# KeyboardMainMCU.net
KiCad netlist of a schematic drawn in Altium Designer
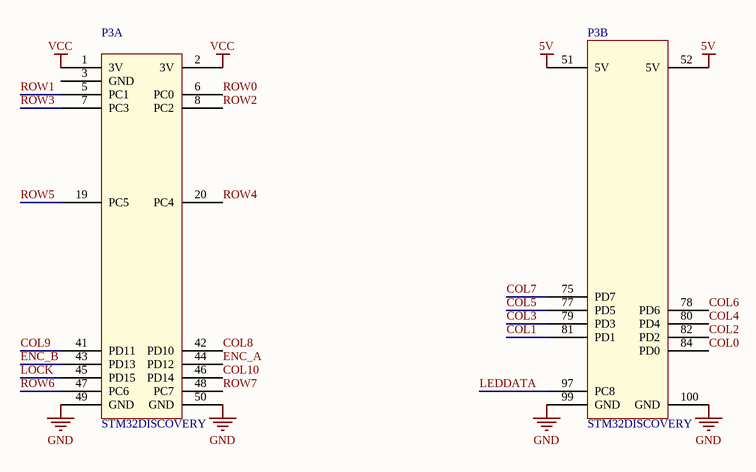
[diagram p0: KeyboardMainMCU.SchDoc]

(export (version "E")
  (design (tool "Eeschema 10.0.6"))
  (components
    (comp (ref "P3")
      (value "STM32DISCOVERY")
      (footprint "DISCO")
      (libsource (lib "OSA") (part "STM32DISCOVERY"))
    )
  )
  (nets
    (net (code "1") (name "/COL0") (class "Default")
      (node (ref "P3") (pin "84") (pinfunction "PD0_84") (pintype "passive"))
    )
    (net (code "2") (name "/COL1") (class "Default")
      (node (ref "P3") (pin "81") (pinfunction "PD1_81") (pintype "passive"))
    )
    (net (code "3") (name "/COL2") (class "Default")
      (node (ref "P3") (pin "82") (pinfunction "PD2_82") (pintype "passive"))
    )
    (net (code "4") (name "/COL3") (class "Default")
      (node (ref "P3") (pin "79") (pinfunction "PD3_79") (pintype "passive"))
    )
    (net (code "5") (name "/COL4") (class "Default")
      (node (ref "P3") (pin "80") (pinfunction "PD4_80") (pintype "passive"))
    )
    (net (code "6") (name "/COL5") (class "Default")
      (node (ref "P3") (pin "77") (pinfunction "PD5_77") (pintype "passive"))
    )
    (net (code "7") (name "/COL6") (class "Default")
      (node (ref "P3") (pin "78") (pinfunction "PD6_78") (pintype "passive"))
    )
    (net (code "8") (name "/COL7") (class "Default")
      (node (ref "P3") (pin "75") (pinfunction "PD7_75") (pintype "passive"))
    )
    (net (code "9") (name "/COL8") (class "Default")
      (node (ref "P3") (pin "42") (pinfunction "PD10_42") (pintype "passive"))
    )
    (net (code "10") (name "/COL9") (class "Default")
      (node (ref "P3") (pin "41") (pinfunction "PD11_41") (pintype "passive"))
    )
    (net (code "11") (name "/COL10") (class "Default")
      (node (ref "P3") (pin "46") (pinfunction "PD14_46") (pintype "passive"))
    )
    (net (code "12") (name "/ENC_A") (class "Default")
      (node (ref "P3") (pin "44") (pinfunction "PD12_44") (pintype "passive"))
    )
    (net (code "13") (name "/ENC_B") (class "Default")
      (node (ref "P3") (pin "43") (pinfunction "PD13_43") (pintype "passive"))
    )
    (net (code "14") (name "/LEDDATA") (class "Default")
      (node (ref "P3") (pin "97") (pinfunction "PC8_97") (pintype "passive"))
    )
    (net (code "15") (name "/LOCK") (class "Default")
      (node (ref "P3") (pin "45") (pinfunction "PD15_45") (pintype "passive"))
    )
    (net (code "16") (name "/ROW0") (class "Default")
      (node (ref "P3") (pin "6") (pinfunction "PC0_6") (pintype "passive"))
    )
    (net (code "17") (name "/ROW1") (class "Default")
      (node (ref "P3") (pin "5") (pinfunction "PC1_5") (pintype "passive"))
    )
    (net (code "18") (name "/ROW2") (class "Default")
      (node (ref "P3") (pin "8") (pinfunction "PC2_8") (pintype "passive"))
    )
    (net (code "19") (name "/ROW3") (class "Default")
      (node (ref "P3") (pin "7") (pinfunction "PC3_7") (pintype "passive"))
    )
    (net (code "20") (name "/ROW4") (class "Default")
      (node (ref "P3") (pin "20") (pinfunction "PC4_20") (pintype "passive"))
    )
    (net (code "21") (name "/ROW5") (class "Default")
      (node (ref "P3") (pin "19") (pinfunction "PC5_19") (pintype "passive"))
    )
    (net (code "22") (name "/ROW6") (class "Default")
      (node (ref "P3") (pin "47") (pinfunction "PC6_47") (pintype "passive"))
    )
    (net (code "23") (name "/ROW7") (class "Default")
      (node (ref "P3") (pin "48") (pinfunction "PC7_48") (pintype "passive"))
    )
    (net (code "24") (name "5V") (class "Default")
      (node (ref "P3") (pin "51") (pinfunction "5V_51") (pintype "passive"))
      (node (ref "P3") (pin "52") (pinfunction "5V_52") (pintype "passive"))
    )
    (net (code "25") (name "GND") (class "Default")
      (node (ref "P3") (pin "100") (pinfunction "GND_100") (pintype "passive"))
      (node (ref "P3") (pin "49") (pinfunction "GND_49") (pintype "passive"))
      (node (ref "P3") (pin "50") (pinfunction "GND_50") (pintype "passive"))
      (node (ref "P3") (pin "99") (pinfunction "GND_99") (pintype "passive"))
    )
    (net (code "26") (name "VCC") (class "Default")
      (node (ref "P3") (pin "1") (pinfunction "3V_1") (pintype "passive"))
      (node (ref "P3") (pin "2") (pinfunction "3V_2") (pintype "passive"))
    )
    (net (code "27") (name "unconnected-(P3A-GND-Pad3)") (class "Default")
      (node (ref "P3") (pin "3") (pinfunction "GND_3") (pintype "passive"))
    )
  )
)
